# Power.net
KiCad netlist of a schematic drawn in Altium Designer
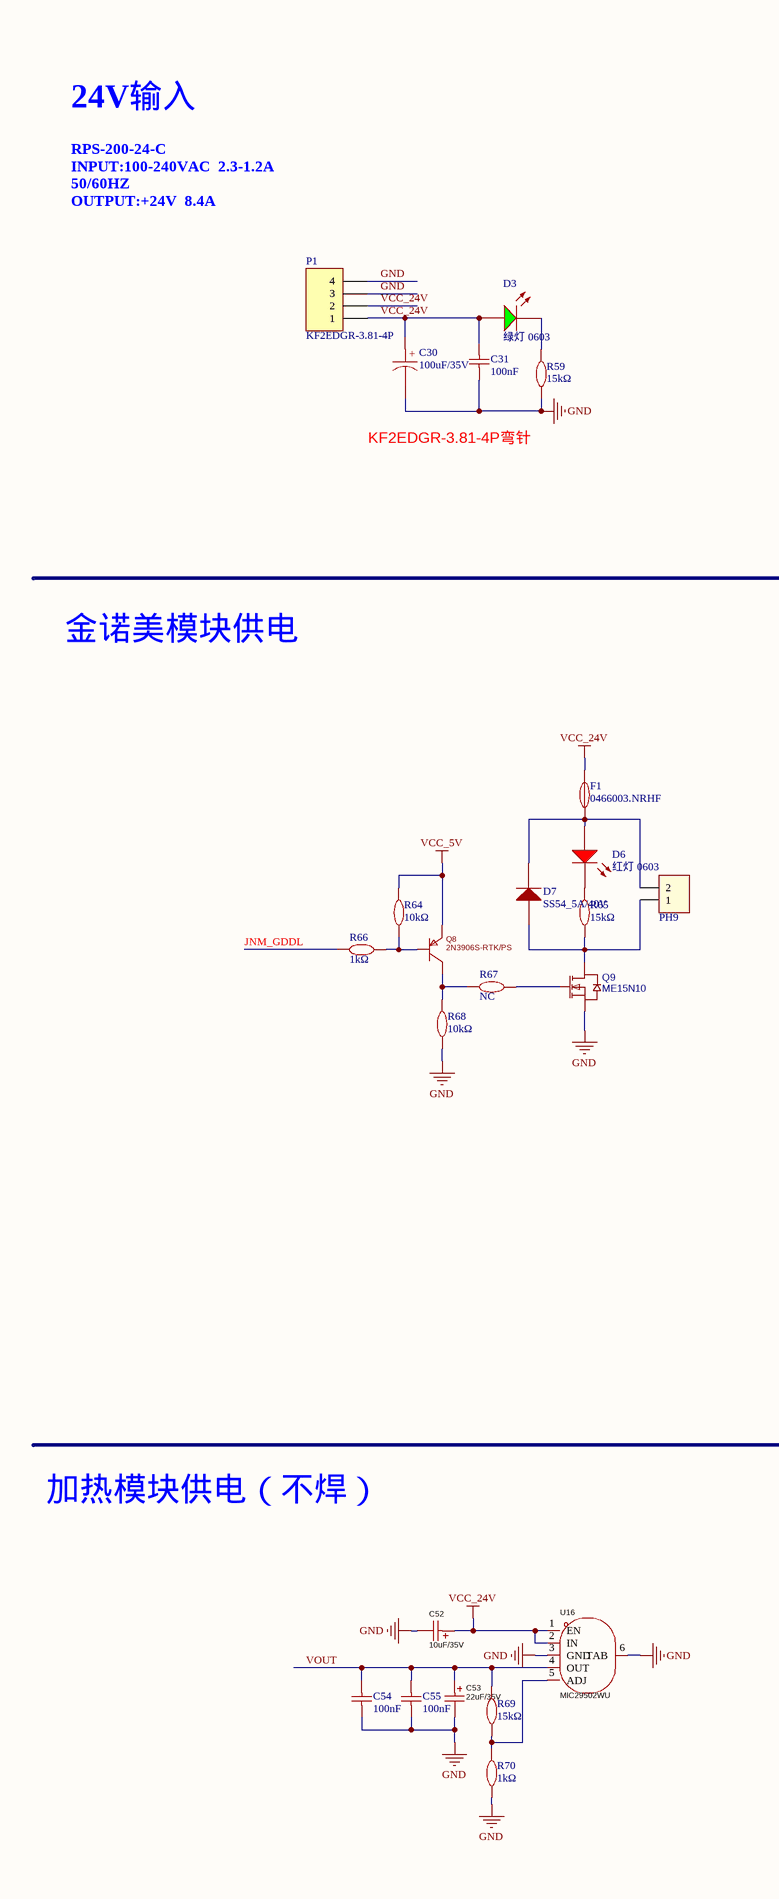
[diagram p0: Power.SchDoc, left]
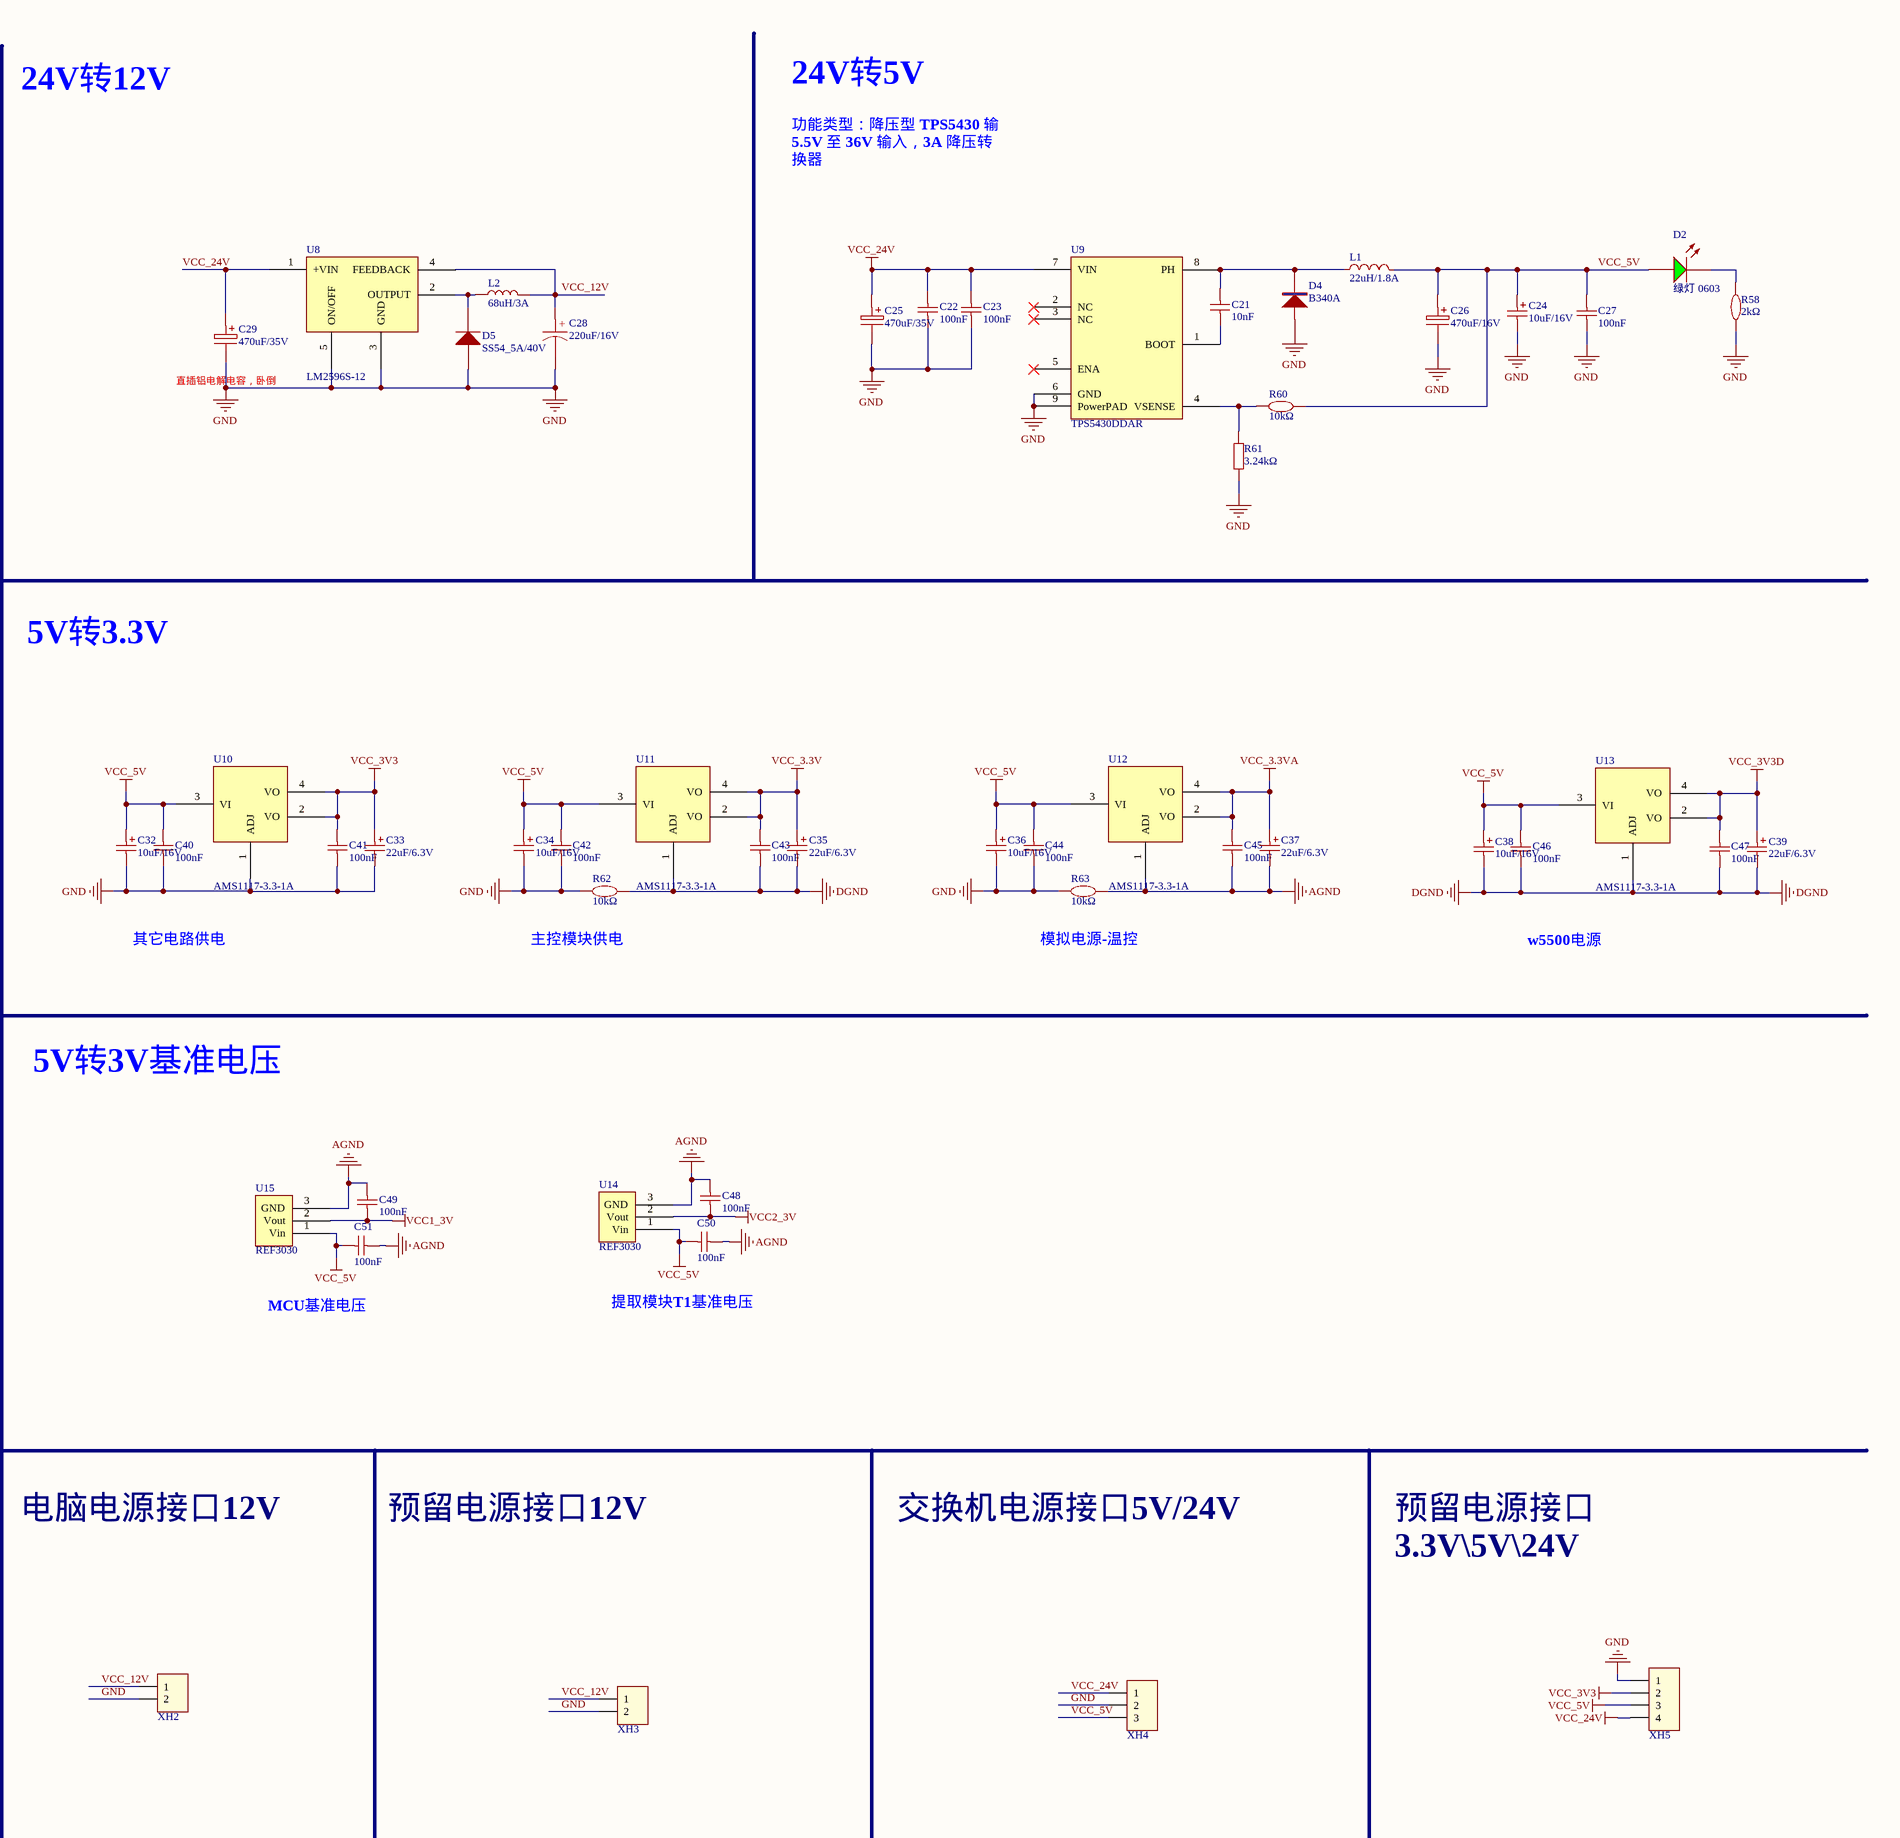
[diagram p1: Power.SchDoc, right]

(export (version "E")
  (design (tool "Eeschema 10.0.6"))
  (components
    (comp (ref "C21")
      (value "10nF")
      (footprint "C0603")
      (description "贴片电容,X7R")
      (libsource (lib "XG_DW_POCT_2K10LED_3") (part "10nF/50V,C0603"))
    )
    (comp (ref "C22")
      (value "100nF")
      (footprint "C0603")
      (description "贴片电容,X7R")
      (libsource (lib "XG_DW_POCT_2K10LED_3") (part "100nF/50V,C0603"))
    )
    (comp (ref "C23")
      (value "100nF")
      (footprint "C0603")
      (description "贴片电容,X7R")
      (libsource (lib "XG_DW_POCT_2K10LED_3") (part "100nF/50V,C0603"))
    )
    (comp (ref "C24")
      (value "10uF/16V")
      (footprint "CASE-A_3216")
      (description "钽电容;±10%;16V")
      (libsource (lib "XG_DW_POCT_2K10LED_3") (part "10uF/16V,CASE-A_3216"))
    )
    (comp (ref "C25")
      (value "470uF/35V")
      (footprint "ELE-S-10.5/D10")
      (description "贴片型铝电解电容")
      (libsource (lib "XG_DW_POCT_2K10LED_3") (part "470uF/35V,D10*10.5mm"))
    )
    (comp (ref "C26")
      (value "470uF/16V")
      (footprint "ELE-S-10.5/D8.0")
      (description "贴片型铝电解电容")
      (libsource (lib "XG_DW_POCT_2K10LED_3") (part "470uF/16V,D8*10.5mm"))
    )
    (comp (ref "C27")
      (value "100nF")
      (footprint "C0603")
      (description "贴片电容,X7R")
      (libsource (lib "XG_DW_POCT_2K10LED_3") (part "100nF/50V,C0603"))
    )
    (comp (ref "C28")
      (value "220uF/16V")
      (footprint "SMD-ECAP-6.3×7.7")
      (description "贴片型铝电解电容")
      (libsource (lib "XG_DW_POCT_2K10LED_3") (part "220uF/16V,SMD,D6.3x7.7mm"))
    )
    (comp (ref "C29")
      (value "470uF/35V")
      (footprint "ELE-S-10.5/D10")
      (description "贴片型铝电解电容")
      (libsource (lib "XG_DW_POCT_2K10LED_3") (part "470uF/35V,D10*10.5mm"))
    )
    (comp (ref "C30")
      (value "100uF/35V")
      (footprint "SMD-ECAP-6.3×7.7")
      (description "贴片型铝电解电容")
      (libsource (lib "XG_DW_POCT_2K10LED_3") (part "100uF/35V,SMD,6.3x7.7mm"))
    )
    (comp (ref "C31")
      (value "100nF")
      (footprint "C0603")
      (description "贴片电容,X7R")
      (libsource (lib "XG_DW_POCT_2K10LED_3") (part "100nF/50V,C0603"))
    )
    (comp (ref "C32")
      (value "10uF/16V")
      (footprint "CASE-A_3216")
      (description "钽电容;±10%;16V")
      (libsource (lib "XG_DW_POCT_2K10LED_3") (part "10uF/16V,CASE-A_3216"))
    )
    (comp (ref "C33")
      (value "22uF/6.3V")
      (footprint "CASE-A_3216")
      (description "钽电容;±10%;6.3V")
      (libsource (lib "XG_DW_POCT_2K10LED_3") (part "22uF/6.3V,CASE-A_3216"))
    )
    (comp (ref "C34")
      (value "10uF/16V")
      (footprint "CASE-A_3216")
      (description "钽电容;±10%;16V")
      (libsource (lib "XG_DW_POCT_2K10LED_3") (part "10uF/16V,CASE-A_3216"))
    )
    (comp (ref "C35")
      (value "22uF/6.3V")
      (footprint "CASE-A_3216")
      (description "钽电容;±10%;6.3V")
      (libsource (lib "XG_DW_POCT_2K10LED_3") (part "22uF/6.3V,CASE-A_3216"))
    )
    (comp (ref "C36")
      (value "10uF/16V")
      (footprint "CASE-A_3216")
      (description "钽电容;±10%;16V")
      (libsource (lib "XG_DW_POCT_2K10LED_3") (part "10uF/16V,CASE-A_3216"))
    )
    (comp (ref "C37")
      (value "22uF/6.3V")
      (footprint "CASE-A_3216")
      (description "钽电容;±10%;6.3V")
      (libsource (lib "XG_DW_POCT_2K10LED_3") (part "22uF/6.3V,CASE-A_3216"))
    )
    (comp (ref "C38")
      (value "10uF/16V")
      (footprint "CASE-A_3216")
      (description "钽电容;±10%;16V")
      (libsource (lib "XG_DW_POCT_2K10LED_3") (part "10uF/16V,CASE-A_3216"))
    )
    (comp (ref "C39")
      (value "22uF/6.3V")
      (footprint "CASE-A_3216")
      (description "钽电容;±10%;6.3V")
      (libsource (lib "XG_DW_POCT_2K10LED_3") (part "22uF/6.3V,CASE-A_3216"))
    )
    (comp (ref "C40")
      (value "100nF")
      (footprint "C0603")
      (description "贴片电容,X7R")
      (libsource (lib "XG_DW_POCT_2K10LED_3") (part "100nF/50V,C0603"))
    )
    (comp (ref "C41")
      (value "100nF")
      (footprint "C0603")
      (description "贴片电容,X7R")
      (libsource (lib "XG_DW_POCT_2K10LED_3") (part "100nF/50V,C0603"))
    )
    (comp (ref "C42")
      (value "100nF")
      (footprint "C0603")
      (description "贴片电容,X7R")
      (libsource (lib "XG_DW_POCT_2K10LED_3") (part "100nF/50V,C0603"))
    )
    (comp (ref "C43")
      (value "100nF")
      (footprint "C0603")
      (description "贴片电容,X7R")
      (libsource (lib "XG_DW_POCT_2K10LED_3") (part "100nF/50V,C0603"))
    )
    (comp (ref "C44")
      (value "100nF")
      (footprint "C0603")
      (description "贴片电容,X7R")
      (libsource (lib "XG_DW_POCT_2K10LED_3") (part "100nF/50V,C0603"))
    )
    (comp (ref "C45")
      (value "100nF")
      (footprint "C0603")
      (description "贴片电容,X7R")
      (libsource (lib "XG_DW_POCT_2K10LED_3") (part "100nF/50V,C0603"))
    )
    (comp (ref "C46")
      (value "100nF")
      (footprint "C0603")
      (description "贴片电容,X7R")
      (libsource (lib "XG_DW_POCT_2K10LED_3") (part "100nF/50V,C0603"))
    )
    (comp (ref "C47")
      (value "100nF")
      (footprint "C0603")
      (description "贴片电容,X7R")
      (libsource (lib "XG_DW_POCT_2K10LED_3") (part "100nF/50V,C0603"))
    )
    (comp (ref "C48")
      (value "100nF")
      (footprint "C0603")
      (description "贴片电容,X7R")
      (libsource (lib "XG_DW_POCT_2K10LED_3") (part "100nF/50V,C0603"))
    )
    (comp (ref "C49")
      (value "100nF")
      (footprint "C0603")
      (description "贴片电容,X7R")
      (libsource (lib "XG_DW_POCT_2K10LED_3") (part "100nF/50V,C0603"))
    )
    (comp (ref "C50")
      (value "100nF")
      (footprint "C0603")
      (description "贴片电容,X7R")
      (libsource (lib "XG_DW_POCT_2K10LED_3") (part "100nF/50V,C0603"))
    )
    (comp (ref "C51")
      (value "100nF")
      (footprint "C0603")
      (description "贴片电容,X7R")
      (libsource (lib "XG_DW_POCT_2K10LED_3") (part "100nF/50V,C0603"))
    )
    (comp (ref "C52")
      (value "10uF/35V")
      (footprint "CASE-D_7343")
      (description "TAJD106K035RNJ;钽电容;容值 10uF;精度 ±10%; 额定电压 35V;等效串联电阻(ESR) 1Ω@100kHz")
      (libsource (lib "XG_DW_POCT_2K10LED_3") (part "10uF/35V,CASE-D-7343"))
    )
    (comp (ref "C53")
      (value "22uF/35V")
      (footprint "CAP-SMD_L7.3-W4.3-RD")
      (description "TAJD226K035RNJ;钽电容;容值 22uF; 精度 ±10%额定电压 35V;等效串联电阻(ESR) 900mΩ@100kHz")
      (libsource (lib "XG_DW_POCT_2K10LED_3") (part "22uF/35V,CASE-D-7343"))
    )
    (comp (ref "C54")
      (value "100nF")
      (footprint "C0805")
      (description "贴片电容,X7R")
      (libsource (lib "XG_DW_POCT_2K10LED_3") (part "100nF/50V,C0805"))
    )
    (comp (ref "C55")
      (value "100nF")
      (footprint "C0805")
      (description "贴片电容,X7R")
      (libsource (lib "XG_DW_POCT_2K10LED_3") (part "100nF/50V,C0805"))
    )
    (comp (ref "D2")
      (value "绿灯 0603")
      (footprint "LED_0603")
      (description "发光二极管")
      (libsource (lib "XG_DW_POCT_2K10LED_3") (part "绿灯 0603"))
    )
    (comp (ref "D3")
      (value "绿灯 0603")
      (footprint "LED_0603")
      (description "发光二极管")
      (libsource (lib "XG_DW_POCT_2K10LED_3") (part "绿灯 0603"))
    )
    (comp (ref "D4")
      (value "B340A")
      (footprint "D-SMA")
      (description "肖特基二极管；正向压降(Vf) 550mV@3A； 直流反向耐压(Vr) 40V； 整流电流 3A； 反向电流(Ir) 500uA@40V")
      (libsource (lib "XG_DW_POCT_2K10LED_3") (part "B340A"))
    )
    (comp (ref "D5")
      (value "SS54_5A/40V")
      (footprint "SMA(DO-214AC)_S5")
      (description "肖特基二极管")
      (libsource (lib "XG_DW_POCT_2K10LED_3") (part "SS54_5A/40V"))
    )
    (comp (ref "D6")
      (value "红灯 0603")
      (footprint "LED_0603")
      (description "发光二极管")
      (libsource (lib "XG_DW_POCT_2K10LED_3") (part "红灯 0603"))
    )
    (comp (ref "D7")
      (value "SS54_5A/40V")
      (footprint "SMA(DO-214AC)_S5")
      (description "肖特基二极管")
      (libsource (lib "XG_DW_POCT_2K10LED_3") (part "SS54_5A/40V"))
    )
    (comp (ref "F1")
      (value "0466003.NRHF")
      (footprint "F1206")
      (description "一次性贴片式保险丝；额定电流 3A；额定电压 (AC) 32V")
      (libsource (lib "XG_DW_POCT_2K10LED_3") (part "0466003.NRHF"))
    )
    (comp (ref "L1")
      (value "22uH/1.8A")
      (footprint "L-6X6X4.5")
      (description "SWPA6045S220MT;功率电感;SMD,6x6mm;电感值 22uH;精度 ±20%;额定电流 1.8A;饱和电流(Isat) 2.2A;直流电阻(DCR) 89mΩ")
      (libsource (lib "XG_DW_POCT_2K10LED_3") (part "22uH/1.8A,L-6X6X4.5"))
    )
    (comp (ref "L2")
      (value "68uH/3A")
      (footprint "SMD INDUCTOR 68uH 3A")
      (description "YSPI1050-680M;功率电感;电感值 68uH;精度 ±20%;额定电流 3A;直流电阻(DCR) 240mΩ")
      (libsource (lib "XG_DW_POCT_2K10LED_3") (part "68uH/3A,SMD,11.5x10mm"))
    )
    (comp (ref "P1")
      (value "KF2EDGR-3.81-4P")
      (footprint "KF2EDGK 3.81mm-4P")
      (description "C441184")
      (libsource (lib "XG_DW_POCT_2K10LED_3") (part "KF2EDGR-3.81-4P"))
    )
    (comp (ref "PH9") (value "PH2.0-2P") (footprint "PH2.0-2P 弯针") (libsource (lib "") (part "PH2.0-2P_1")))
    (comp (ref "Q8")
      (value "2N3906S-RTK/PS")
      (footprint "SOT-23-3_L2.9-W1.3-P1.90-LS2.4-TR")
      (fields (field (name "MANUFACTURER") "KEC"))
      (libsource (lib "XG_DW_POCT_2K10LED_3") (part "2N3906S-RTK/PS"))
    )
    (comp (ref "Q9")
      (value "ME15N10")
      (footprint "TO-252-2_L6.6-W6.1-P4.57-LS9.9-TL-CW")
      (description "场效应管(MOSFET);N沟道")
      (libsource (lib "XG_DW_POCT_2K10LED_3") (part "ME15N10"))
    )
    (comp (ref "R58")
      (value "2kΩ")
      (footprint "R0603")
      (description "贴片电阻")
      (libsource (lib "XG_DW_POCT_2K10LED_3") (part "2kΩ,R0603"))
    )
    (comp (ref "R59")
      (value "15kΩ")
      (footprint "R0603")
      (description "贴片电阻")
      (libsource (lib "XG_DW_POCT_2K10LED_3") (part "15kΩ,R0603"))
    )
    (comp (ref "R60")
      (value "10kΩ")
      (footprint "R0603")
      (description "电阻类型:厚膜电阻;阻值:10kΩ;精度:±1%;功率:100mW;最大工作电压:75V;温度系数:±100ppm/℃;")
      (libsource (lib "XG_DW_POCT_2K10LED_3") (part "10kΩ,R0603"))
    )
    (comp (ref "R61")
      (value "3.24kΩ")
      (footprint "R0603")
      (description "贴片电阻3.24KΩ;1%")
      (libsource (lib "XG_DW_POCT_2K10LED_3") (part "3.24kΩ,R0603"))
    )
    (comp (ref "R62")
      (value "10kΩ")
      (footprint "R1206")
      (description "贴片电阻")
      (libsource (lib "altium-import") (part "root_0_10kΩ,R1206_"))
    )
    (comp (ref "R63")
      (value "10kΩ")
      (footprint "R1206")
      (description "贴片电阻")
      (libsource (lib "altium-import") (part "root_0_10kΩ,R1206_"))
    )
    (comp (ref "R64")
      (value "10kΩ")
      (footprint "R0603")
      (description "电阻类型:厚膜电阻;阻值:10kΩ;精度:±1%;功率:100mW;最大工作电压:75V;温度系数:±100ppm/℃;")
      (libsource (lib "XG_DW_POCT_2K10LED_3") (part "10kΩ,R0603"))
    )
    (comp (ref "R65")
      (value "15kΩ")
      (footprint "R0603")
      (description "贴片电阻")
      (libsource (lib "XG_DW_POCT_2K10LED_3") (part "15kΩ,R0603"))
    )
    (comp (ref "R66")
      (value "1kΩ")
      (footprint "R0603")
      (description "电阻类型:厚膜电阻;阻值:1kΩ;精度:±1%;功率:125mW;最大工作电压:150V;温度系数:±100ppm/℃;")
      (libsource (lib "XG_DW_POCT_2K10LED_3") (part "1kΩ,R0603"))
    )
    (comp (ref "R67")
      (value "NC")
      (footprint "R0603")
      (libsource (lib "XG_DW_POCT_2K10LED_3") (part "NC,R0603"))
    )
    (comp (ref "R68")
      (value "10kΩ")
      (footprint "R0603")
      (description "电阻类型:厚膜电阻;阻值:10kΩ;精度:±1%;功率:100mW;最大工作电压:75V;温度系数:±100ppm/℃;")
      (libsource (lib "XG_DW_POCT_2K10LED_3") (part "10kΩ,R0603"))
    )
    (comp (ref "R69")
      (value "15kΩ")
      (footprint "R1206")
      (description "贴片电阻")
      (libsource (lib "XG_DW_POCT_2K10LED_3") (part "15kΩ,R1206"))
    )
    (comp (ref "R70")
      (value "1kΩ")
      (footprint "R1206")
      (description "贴片电阻")
      (libsource (lib "XG_DW_POCT_2K10LED_3") (part "1kΩ,R1206"))
    )
    (comp (ref "U8")
      (value "LM2596S-12")
      (footprint "TO-263-5")
      (libsource (lib "XG_DW_POCT_2K10LED_3") (part "LM2596S-12"))
    )
    (comp (ref "U9")
      (value "TPS5430DDAR")
      (footprint "IC-SO8-PAD")
      (description "DC-DC电源芯片；降压型；可调； 工作电压 5.5V~36V；输出电压 1.221V~32.04V；输出电流 3A\r\n\r\n开关频率 500kHz")
      (libsource (lib "XG_DW_POCT_2K10LED_3") (part "TPS5430DDAR"))
    )
    (comp (ref "U10")
      (value "AMS1117-3.3-1A")
      (footprint "LM1117I(SOT223)")
      (description "800mA Low Dropout Regulator")
      (libsource (lib "XG_DW_POCT_2K10LED_3") (part "AMS1117-3.3-1A"))
    )
    (comp (ref "U11")
      (value "AMS1117-3.3-1A")
      (footprint "LM1117I(SOT223)")
      (description "800mA Low Dropout Regulator")
      (libsource (lib "XG_DW_POCT_2K10LED_3") (part "AMS1117-3.3-1A"))
    )
    (comp (ref "U12")
      (value "AMS1117-3.3-1A")
      (footprint "LM1117I(SOT223)")
      (description "800mA Low Dropout Regulator")
      (libsource (lib "XG_DW_POCT_2K10LED_3") (part "AMS1117-3.3-1A"))
    )
    (comp (ref "U13")
      (value "AMS1117-3.3-1A")
      (footprint "LM1117I(SOT223)")
      (description "800mA Low Dropout Regulator")
      (libsource (lib "XG_DW_POCT_2K10LED_3") (part "AMS1117-3.3-1A"))
    )
    (comp (ref "U14")
      (value "REF3030")
      (footprint "SOT-23(SOT-23-3)")
      (description "REF3030AIDBZR/REF3030AIDBZT")
      (libsource (lib "XG_DW_POCT_2K10LED_3") (part "REF3030"))
    )
    (comp (ref "U15")
      (value "REF3030")
      (footprint "SOT-23(SOT-23-3)")
      (description "REF3030AIDBZR/REF3030AIDBZT")
      (libsource (lib "XG_DW_POCT_2K10LED_3") (part "REF3030"))
    )
    (comp (ref "U16")
      (value "MIC29502WU")
      (footprint "TO-263-5_L10.2-W9.9-P1.70-LS14.4-TL")
      (description "线性稳压器(LDO)")
      (libsource (lib "XG_DW_POCT_2K10LED_3") (part "MIC29502WU"))
    )
    (comp (ref "XH2")
      (value "PH2.0-2P")
      (footprint "PH2.0-2P 弯针")
      (libsource (lib "XG_DW_POCT_2K10LED_3") (part "PH2.0-2P"))
    )
    (comp (ref "XH3")
      (value "PH2.0-2P")
      (footprint "PH2.0-2P 弯针")
      (libsource (lib "XG_DW_POCT_2K10LED_3") (part "PH2.0-2P"))
    )
    (comp (ref "XH4")
      (value "PH2.0-3P")
      (footprint "PH2.0-3P 弯针")
      (libsource (lib "XG_DW_POCT_2K10LED_3") (part "PH2.0-3P"))
    )
    (comp (ref "XH5")
      (value "PH2.0-4P")
      (footprint "PH2.0-4P 弯针")
      (libsource (lib "XG_DW_POCT_2K10LED_3") (part "PH2.0-4P"))
    )
  )
  (nets
    (net (code "1") (name "/JNM_GDDL") (class "Default")
      (node (ref "R66") (pin "1") (pinfunction "1_1") (pintype "passive"))
    )
    (net (code "2") (name "/VCC_12V") (class "Default")
      (node (ref "C28") (pin "1") (pinfunction "1_1") (pintype "passive"))
      (node (ref "L2") (pin "2") (pinfunction "2_2") (pintype "passive"))
      (node (ref "U8") (pin "4") (pinfunction "FEEDBACK_4") (pintype "passive"))
      (node (ref "XH2") (pin "1") (pinfunction "1_1") (pintype "passive"))
      (node (ref "XH3") (pin "1") (pinfunction "1_1") (pintype "passive"))
    )
    (net (code "3") (name "/VOUT") (class "Default")
      (node (ref "C53") (pin "1") (pinfunction "1_1") (pintype "passive"))
      (node (ref "C54") (pin "2") (pinfunction "2_2") (pintype "passive"))
      (node (ref "C55") (pin "2") (pinfunction "2_2") (pintype "passive"))
      (node (ref "R69") (pin "1") (pinfunction "1_1") (pintype "passive"))
      (node (ref "U16") (pin "4") (pinfunction "OUT_4") (pintype "passive"))
    )
    (net (code "4") (name "AGND") (class "Default")
      (node (ref "C37") (pin "2") (pinfunction "2_2") (pintype "passive"))
      (node (ref "C45") (pin "1") (pinfunction "1_1") (pintype "passive"))
      (node (ref "C48") (pin "2") (pinfunction "2_2") (pintype "passive"))
      (node (ref "C49") (pin "2") (pinfunction "2_2") (pintype "passive"))
      (node (ref "C50") (pin "2") (pinfunction "2_2") (pintype "passive"))
      (node (ref "C51") (pin "2") (pinfunction "2_2") (pintype "passive"))
      (node (ref "R63") (pin "2") (pinfunction "2_2") (pintype "passive"))
      (node (ref "U12") (pin "1") (pinfunction "ADJ_1") (pintype "passive"))
      (node (ref "U14") (pin "3") (pinfunction "GND_3") (pintype "passive"))
      (node (ref "U15") (pin "3") (pinfunction "GND_3") (pintype "passive"))
    )
    (net (code "5") (name "DGND") (class "Default")
      (node (ref "C35") (pin "2") (pinfunction "2_2") (pintype "passive"))
      (node (ref "C38") (pin "2") (pinfunction "2_2") (pintype "passive"))
      (node (ref "C39") (pin "2") (pinfunction "2_2") (pintype "passive"))
      (node (ref "C43") (pin "1") (pinfunction "1_1") (pintype "passive"))
      (node (ref "C46") (pin "1") (pinfunction "1_1") (pintype "passive"))
      (node (ref "C47") (pin "1") (pinfunction "1_1") (pintype "passive"))
      (node (ref "R62") (pin "2") (pinfunction "2_2") (pintype "passive"))
      (node (ref "U11") (pin "1") (pinfunction "ADJ_1") (pintype "passive"))
      (node (ref "U13") (pin "1") (pinfunction "ADJ_1") (pintype "passive"))
    )
    (net (code "6") (name "GND") (class "Default")
      (node (ref "C22") (pin "1") (pinfunction "1_1") (pintype "passive"))
      (node (ref "C23") (pin "1") (pinfunction "1_1") (pintype "passive"))
      (node (ref "C24") (pin "2") (pinfunction "2_2") (pintype "passive"))
      (node (ref "C25") (pin "2") (pinfunction "2_2") (pintype "passive"))
      (node (ref "C26") (pin "2") (pinfunction "2_2") (pintype "passive"))
      (node (ref "C27") (pin "1") (pinfunction "1_1") (pintype "passive"))
      (node (ref "C28") (pin "2") (pinfunction "2_2") (pintype "passive"))
      (node (ref "C29") (pin "2") (pinfunction "2_2") (pintype "passive"))
      (node (ref "C30") (pin "2") (pinfunction "2_2") (pintype "passive"))
      (node (ref "C31") (pin "1") (pinfunction "1_1") (pintype "passive"))
      (node (ref "C32") (pin "2") (pinfunction "2_2") (pintype "passive"))
      (node (ref "C33") (pin "2") (pinfunction "2_2") (pintype "passive"))
      (node (ref "C34") (pin "2") (pinfunction "2_2") (pintype "passive"))
      (node (ref "C36") (pin "2") (pinfunction "2_2") (pintype "passive"))
      (node (ref "C40") (pin "1") (pinfunction "1_1") (pintype "passive"))
      (node (ref "C41") (pin "1") (pinfunction "1_1") (pintype "passive"))
      (node (ref "C42") (pin "1") (pinfunction "1_1") (pintype "passive"))
      (node (ref "C44") (pin "1") (pinfunction "1_1") (pintype "passive"))
      (node (ref "C52") (pin "2") (pinfunction "2_2") (pintype "passive"))
      (node (ref "C53") (pin "2") (pinfunction "2_2") (pintype "passive"))
      (node (ref "C54") (pin "1") (pinfunction "1_1") (pintype "passive"))
      (node (ref "C55") (pin "1") (pinfunction "1_1") (pintype "passive"))
      (node (ref "D4") (pin "1") (pinfunction "1_1") (pintype "passive"))
      (node (ref "D5") (pin "1") (pinfunction "A_1") (pintype "passive"))
      (node (ref "P1") (pin "3") (pinfunction "3_3") (pintype "passive"))
      (node (ref "P1") (pin "4") (pinfunction "4_4") (pintype "passive"))
      (node (ref "Q9") (pin "3") (pinfunction "S_3") (pintype "passive"))
      (node (ref "R58") (pin "2") (pinfunction "2_2") (pintype "passive"))
      (node (ref "R59") (pin "1") (pinfunction "1_1") (pintype "passive"))
      (node (ref "R61") (pin "1") (pinfunction "1_1") (pintype "passive"))
      (node (ref "R62") (pin "1") (pinfunction "1_1") (pintype "passive"))
      (node (ref "R63") (pin "1") (pinfunction "1_1") (pintype "passive"))
      (node (ref "R68") (pin "2") (pinfunction "2_2") (pintype "passive"))
      (node (ref "R70") (pin "2") (pinfunction "2_2") (pintype "passive"))
      (node (ref "U10") (pin "1") (pinfunction "ADJ_1") (pintype "passive"))
      (node (ref "U16") (pin "3") (pinfunction "GND_3") (pintype "passive"))
      (node (ref "U16") (pin "6") (pinfunction "TAB_6") (pintype "passive"))
      (node (ref "U8") (pin "3") (pinfunction "GND_3") (pintype "passive"))
      (node (ref "U8") (pin "5") (pinfunction "ON/OFF_5") (pintype "passive"))
      (node (ref "U9") (pin "6") (pinfunction "GND_6") (pintype "passive"))
      (node (ref "U9") (pin "9") (pinfunction "PowerPAD_9") (pintype "passive"))
      (node (ref "XH2") (pin "2") (pinfunction "2_2") (pintype "passive"))
      (node (ref "XH3") (pin "2") (pinfunction "2_2") (pintype "passive"))
      (node (ref "XH4") (pin "2") (pinfunction "2_2") (pintype "passive"))
      (node (ref "XH5") (pin "1") (pinfunction "1_1") (pintype "passive"))
    )
    (net (code "7") (name "Net-(D2-PadK)") (class "Default")
      (node (ref "D2") (pin "K") (pinfunction "K_K") (pintype "passive"))
      (node (ref "R58") (pin "1") (pinfunction "1_1") (pintype "passive"))
    )
    (net (code "8") (name "Net-(D3-PadK)") (class "Default")
      (node (ref "D3") (pin "K") (pinfunction "K_K") (pintype "passive"))
      (node (ref "R59") (pin "2") (pinfunction "2_2") (pintype "passive"))
    )
    (net (code "9") (name "Net-(D5-K)") (class "Default")
      (node (ref "D5") (pin "2") (pinfunction "K_2") (pintype "passive"))
      (node (ref "L2") (pin "1") (pinfunction "1_1") (pintype "passive"))
      (node (ref "U8") (pin "2") (pinfunction "OUTPUT_2") (pintype "passive"))
    )
    (net (code "10") (name "Net-(D6-PadK)") (class "Default")
      (node (ref "D6") (pin "K") (pinfunction "K_K") (pintype "passive"))
      (node (ref "R65") (pin "2") (pinfunction "2_2") (pintype "passive"))
    )
    (net (code "11") (name "Net-(D7-A)") (class "Default")
      (node (ref "D7") (pin "1") (pinfunction "A_1") (pintype "passive"))
      (node (ref "PH9") (pin "1") (pinfunction "1_1") (pintype "passive"))
      (node (ref "Q9") (pin "2") (pinfunction "D_2") (pintype "passive"))
      (node (ref "R65") (pin "1") (pinfunction "1_1") (pintype "passive"))
    )
    (net (code "12") (name "Net-(D7-K)") (class "Default")
      (node (ref "D6") (pin "A") (pinfunction "A_A") (pintype "passive"))
      (node (ref "D7") (pin "2") (pinfunction "K_2") (pintype "passive"))
      (node (ref "F1") (pin "1") (pinfunction "1_1") (pintype "passive"))
      (node (ref "PH9") (pin "2") (pinfunction "2_2") (pintype "passive"))
    )
    (net (code "13") (name "Net-(Q8-B)") (class "Default")
      (node (ref "Q8") (pin "2") (pinfunction "B_2") (pintype "passive"))
      (node (ref "R64") (pin "2") (pinfunction "2_2") (pintype "passive"))
      (node (ref "R66") (pin "2") (pinfunction "2_2") (pintype "passive"))
    )
    (net (code "14") (name "Net-(Q8-C)") (class "Default")
      (node (ref "Q8") (pin "3") (pinfunction "C_3") (pintype "passive"))
      (node (ref "R67") (pin "1") (pinfunction "1_1") (pintype "passive"))
      (node (ref "R68") (pin "1") (pinfunction "1_1") (pintype "passive"))
    )
    (net (code "15") (name "Net-(Q9-G)") (class "Default")
      (node (ref "Q9") (pin "1") (pinfunction "G_1") (pintype "passive"))
      (node (ref "R67") (pin "2") (pinfunction "2_2") (pintype "passive"))
    )
    (net (code "16") (name "Net-(U9-BOOT)") (class "Default")
      (node (ref "C21") (pin "1") (pinfunction "1_1") (pintype "passive"))
      (node (ref "U9") (pin "1") (pinfunction "BOOT_1") (pintype "passive"))
    )
    (net (code "17") (name "Net-(U9-PH)") (class "Default")
      (node (ref "C21") (pin "2") (pinfunction "2_2") (pintype "passive"))
      (node (ref "D4") (pin "2") (pinfunction "2_2") (pintype "passive"))
      (node (ref "L1") (pin "2") (pinfunction "2_2") (pintype "passive"))
      (node (ref "U9") (pin "8") (pinfunction "PH_8") (pintype "passive"))
    )
    (net (code "18") (name "Net-(U9-VSENSE)") (class "Default")
      (node (ref "R60") (pin "2") (pinfunction "2_2") (pintype "passive"))
      (node (ref "R61") (pin "2") (pinfunction "2_2") (pintype "passive"))
      (node (ref "U9") (pin "4") (pinfunction "VSENSE_4") (pintype "passive"))
    )
    (net (code "19") (name "Net-(U16-ADJ)") (class "Default")
      (node (ref "R69") (pin "2") (pinfunction "2_2") (pintype "passive"))
      (node (ref "R70") (pin "1") (pinfunction "1_1") (pintype "passive"))
      (node (ref "U16") (pin "5") (pinfunction "ADJ_5") (pintype "passive"))
    )
    (net (code "20") (name "VCC1_3V") (class "Default")
      (node (ref "C49") (pin "1") (pinfunction "1_1") (pintype "passive"))
      (node (ref "U15") (pin "2") (pinfunction "Vout_2") (pintype "passive"))
    )
    (net (code "21") (name "VCC2_3V") (class "Default")
      (node (ref "C48") (pin "1") (pinfunction "1_1") (pintype "passive"))
      (node (ref "U14") (pin "2") (pinfunction "Vout_2") (pintype "passive"))
    )
    (net (code "22") (name "VCC_3.3V") (class "Default")
      (node (ref "C35") (pin "1") (pinfunction "1_1") (pintype "passive"))
      (node (ref "C43") (pin "2") (pinfunction "2_2") (pintype "passive"))
      (node (ref "U11") (pin "2") (pinfunction "VO_2") (pintype "passive"))
      (node (ref "U11") (pin "4") (pinfunction "VO_4") (pintype "passive"))
    )
    (net (code "23") (name "VCC_3.3VA") (class "Default")
      (node (ref "C37") (pin "1") (pinfunction "1_1") (pintype "passive"))
      (node (ref "C45") (pin "2") (pinfunction "2_2") (pintype "passive"))
      (node (ref "U12") (pin "2") (pinfunction "VO_2") (pintype "passive"))
      (node (ref "U12") (pin "4") (pinfunction "VO_4") (pintype "passive"))
    )
    (net (code "24") (name "VCC_3V3") (class "Default")
      (node (ref "C33") (pin "1") (pinfunction "1_1") (pintype "passive"))
      (node (ref "C41") (pin "2") (pinfunction "2_2") (pintype "passive"))
      (node (ref "U10") (pin "2") (pinfunction "VO_2") (pintype "passive"))
      (node (ref "U10") (pin "4") (pinfunction "VO_4") (pintype "passive"))
      (node (ref "XH5") (pin "2") (pinfunction "2_2") (pintype "passive"))
    )
    (net (code "25") (name "VCC_3V3D") (class "Default")
      (node (ref "C39") (pin "1") (pinfunction "1_1") (pintype "passive"))
      (node (ref "C47") (pin "2") (pinfunction "2_2") (pintype "passive"))
      (node (ref "U13") (pin "2") (pinfunction "VO_2") (pintype "passive"))
      (node (ref "U13") (pin "4") (pinfunction "VO_4") (pintype "passive"))
    )
    (net (code "26") (name "VCC_5V") (class "Default")
      (node (ref "C24") (pin "1") (pinfunction "1_1") (pintype "passive"))
      (node (ref "C26") (pin "1") (pinfunction "1_1") (pintype "passive"))
      (node (ref "C27") (pin "2") (pinfunction "2_2") (pintype "passive"))
      (node (ref "C32") (pin "1") (pinfunction "1_1") (pintype "passive"))
      (node (ref "C34") (pin "1") (pinfunction "1_1") (pintype "passive"))
      (node (ref "C36") (pin "1") (pinfunction "1_1") (pintype "passive"))
      (node (ref "C38") (pin "1") (pinfunction "1_1") (pintype "passive"))
      (node (ref "C40") (pin "2") (pinfunction "2_2") (pintype "passive"))
      (node (ref "C42") (pin "2") (pinfunction "2_2") (pintype "passive"))
      (node (ref "C44") (pin "2") (pinfunction "2_2") (pintype "passive"))
      (node (ref "C46") (pin "2") (pinfunction "2_2") (pintype "passive"))
      (node (ref "C50") (pin "1") (pinfunction "1_1") (pintype "passive"))
      (node (ref "C51") (pin "1") (pinfunction "1_1") (pintype "passive"))
      (node (ref "D2") (pin "A") (pinfunction "A_A") (pintype "passive"))
      (node (ref "L1") (pin "1") (pinfunction "1_1") (pintype "passive"))
      (node (ref "Q8") (pin "1") (pinfunction "E_1") (pintype "passive"))
      (node (ref "R60") (pin "1") (pinfunction "1_1") (pintype "passive"))
      (node (ref "R64") (pin "1") (pinfunction "1_1") (pintype "passive"))
      (node (ref "U10") (pin "3") (pinfunction "VI_3") (pintype "passive"))
      (node (ref "U11") (pin "3") (pinfunction "VI_3") (pintype "passive"))
      (node (ref "U12") (pin "3") (pinfunction "VI_3") (pintype "passive"))
      (node (ref "U13") (pin "3") (pinfunction "VI_3") (pintype "passive"))
      (node (ref "U14") (pin "1") (pinfunction "Vin_1") (pintype "passive"))
      (node (ref "U15") (pin "1") (pinfunction "Vin_1") (pintype "passive"))
      (node (ref "XH4") (pin "3") (pinfunction "3_3") (pintype "passive"))
      (node (ref "XH5") (pin "3") (pinfunction "3_3") (pintype "passive"))
    )
    (net (code "27") (name "VCC_24V") (class "Default")
      (node (ref "C22") (pin "2") (pinfunction "2_2") (pintype "passive"))
      (node (ref "C23") (pin "2") (pinfunction "2_2") (pintype "passive"))
      (node (ref "C25") (pin "1") (pinfunction "1_1") (pintype "passive"))
      (node (ref "C29") (pin "1") (pinfunction "1_1") (pintype "passive"))
      (node (ref "C30") (pin "1") (pinfunction "1_1") (pintype "passive"))
      (node (ref "C31") (pin "2") (pinfunction "2_2") (pintype "passive"))
      (node (ref "C52") (pin "1") (pinfunction "1_1") (pintype "passive"))
      (node (ref "D3") (pin "A") (pinfunction "A_A") (pintype "passive"))
      (node (ref "F1") (pin "2") (pinfunction "2_2") (pintype "passive"))
      (node (ref "P1") (pin "1") (pinfunction "1_1") (pintype "passive"))
      (node (ref "P1") (pin "2") (pinfunction "2_2") (pintype "passive"))
      (node (ref "U16") (pin "1") (pinfunction "EN_1") (pintype "passive"))
      (node (ref "U16") (pin "2") (pinfunction "IN_2") (pintype "passive"))
      (node (ref "U8") (pin "1") (pinfunction "+VIN_1") (pintype "passive"))
      (node (ref "U9") (pin "7") (pinfunction "VIN_7") (pintype "passive"))
      (node (ref "XH4") (pin "1") (pinfunction "1_1") (pintype "passive"))
      (node (ref "XH5") (pin "4") (pinfunction "4_4") (pintype "passive"))
    )
    (net (code "28") (name "unconnected-(U9-ENA-Pad5)") (class "Default")
      (node (ref "U9") (pin "5") (pinfunction "ENA_5") (pintype "passive+no_connect"))
    )
    (net (code "29") (name "unconnected-(U9-NC-Pad2)") (class "Default")
      (node (ref "U9") (pin "2") (pinfunction "NC_2") (pintype "passive+no_connect"))
    )
    (net (code "30") (name "unconnected-(U9-NC-Pad3)") (class "Default")
      (node (ref "U9") (pin "3") (pinfunction "NC_3") (pintype "passive+no_connect"))
    )
  )
)
